# Audio_Keys.net
KiCad netlist of a schematic drawn in Altium Designer
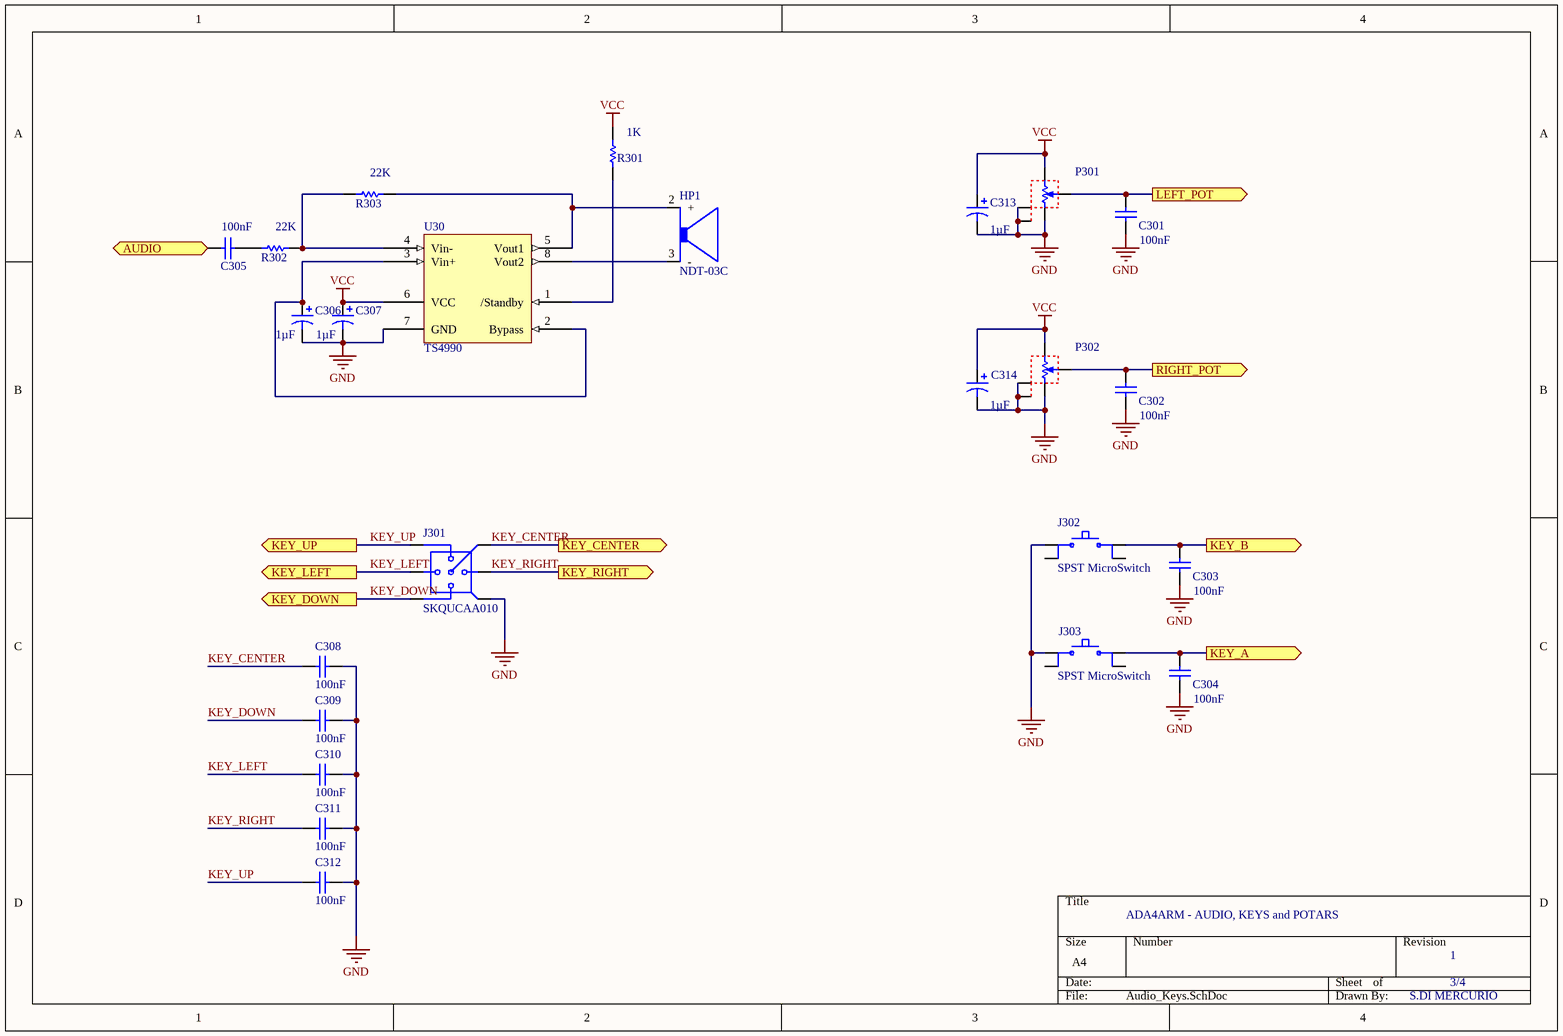
[diagram p0: Audio_Keys.SchDoc]

(export (version "E")
  (design (tool "Eeschema 10.0.6"))
  (components
    (comp (ref "C301")
      (value "100nF")
      (footprint "CAPC1206(3216)100_N")
      (description "CAP 100nF 16V -20% to +80% 1206 (3216 Metric) Thickness 1mm SMD")
      (fields (field (name "TOLERANCE") "-20% to +80%") (field (name "Comment") "CAP 100nF 16V 1206(3216)"))
      (libsource (lib "Altium Content Vault") (part "CMP-1037-04185-1"))
    )
    (comp (ref "C302")
      (value "100nF")
      (footprint "CAPC1206(3216)100_N")
      (description "CAP 100nF 16V -20% to +80% 1206 (3216 Metric) Thickness 1mm SMD")
      (fields (field (name "TOLERANCE") "-20% to +80%") (field (name "Comment") "CAP 100nF 16V 1206(3216)"))
      (libsource (lib "Altium Content Vault") (part "CMP-1037-04185-1"))
    )
    (comp (ref "C303")
      (value "100nF")
      (footprint "CAPC1206(3216)100_N")
      (description "CAP 100nF 16V -20% to +80% 1206 (3216 Metric) Thickness 1mm SMD")
      (fields (field (name "TOLERANCE") "-20% to +80%") (field (name "Comment") "CAP 100nF 16V 1206(3216)"))
      (libsource (lib "Altium Content Vault") (part "CMP-1037-04185-1"))
    )
    (comp (ref "C304")
      (value "100nF")
      (footprint "CAPC1206(3216)100_N")
      (description "CAP 100nF 16V -20% to +80% 1206 (3216 Metric) Thickness 1mm SMD")
      (fields (field (name "TOLERANCE") "-20% to +80%") (field (name "Comment") "CAP 100nF 16V 1206(3216)"))
      (libsource (lib "Altium Content Vault") (part "CMP-1037-04185-1"))
    )
    (comp (ref "C305")
      (value "100nF")
      (footprint "CAPC1206(3216)100_N")
      (description "CAP 100nF 16V -20% to +80% 1206 (3216 Metric) Thickness 1mm SMD")
      (fields (field (name "TOLERANCE") "-20% to +80%") (field (name "Comment") "CAP 100nF 16V 1206(3216)"))
      (libsource (lib "Altium Content Vault") (part "CMP-1037-04185-1"))
    )
    (comp (ref "C306")
      (value "1µF")
      (footprint "EAI 3216-18 A")
      (description "Polarized Capacitor (Surface Mount)")
      (fields (field (name "Comment") "Cap Pol3") (field (name "PUBLISHER") "Altium Limited"))
      (libsource (lib "Miscellaneous Devices") (part "Cap Pol3"))
    )
    (comp (ref "C307")
      (value "1µF")
      (footprint "EAI 3216-18 A")
      (description "Polarized Capacitor (Surface Mount)")
      (fields (field (name "Comment") "Cap Pol3") (field (name "PUBLISHER") "Altium Limited"))
      (libsource (lib "Miscellaneous Devices") (part "Cap Pol3"))
    )
    (comp (ref "C308")
      (value "100nF")
      (footprint "CAPC1206(3216)100_N")
      (description "CAP 100nF 16V -20% to +80% 1206 (3216 Metric) Thickness 1mm SMD")
      (fields (field (name "TOLERANCE") "-20% to +80%") (field (name "Comment") "CAP 100nF 16V 1206(3216)"))
      (libsource (lib "Altium Content Vault") (part "CMP-1037-04185-1"))
    )
    (comp (ref "C309")
      (value "100nF")
      (footprint "CAPC1206(3216)100_N")
      (description "CAP 100nF 16V -20% to +80% 1206 (3216 Metric) Thickness 1mm SMD")
      (fields (field (name "TOLERANCE") "-20% to +80%") (field (name "Comment") "CAP 100nF 16V 1206(3216)"))
      (libsource (lib "Altium Content Vault") (part "CMP-1037-04185-1"))
    )
    (comp (ref "C310")
      (value "100nF")
      (footprint "CAPC1206(3216)100_N")
      (description "CAP 100nF 16V -20% to +80% 1206 (3216 Metric) Thickness 1mm SMD")
      (fields (field (name "TOLERANCE") "-20% to +80%") (field (name "Comment") "CAP 100nF 16V 1206(3216)"))
      (libsource (lib "Altium Content Vault") (part "CMP-1037-04185-1"))
    )
    (comp (ref "C311")
      (value "100nF")
      (footprint "CAPC1206(3216)100_N")
      (description "CAP 100nF 16V -20% to +80% 1206 (3216 Metric) Thickness 1mm SMD")
      (fields (field (name "TOLERANCE") "-20% to +80%") (field (name "Comment") "CAP 100nF 16V 1206(3216)"))
      (libsource (lib "Altium Content Vault") (part "CMP-1037-04185-1"))
    )
    (comp (ref "C312")
      (value "100nF")
      (footprint "CAPC1206(3216)100_N")
      (description "CAP 100nF 16V -20% to +80% 1206 (3216 Metric) Thickness 1mm SMD")
      (fields (field (name "TOLERANCE") "-20% to +80%") (field (name "Comment") "CAP 100nF 16V 1206(3216)"))
      (libsource (lib "Altium Content Vault") (part "CMP-1037-04185-1"))
    )
    (comp (ref "C313")
      (value "1µF")
      (footprint "EAI 3216-18 A")
      (description "Polarized Capacitor (Surface Mount)")
      (fields (field (name "Comment") "Cap Pol3") (field (name "PUBLISHER") "Altium Limited"))
      (libsource (lib "Miscellaneous Devices") (part "Cap Pol3"))
    )
    (comp (ref "C314")
      (value "1µF")
      (footprint "EAI 3216-18 A")
      (description "Polarized Capacitor (Surface Mount)")
      (fields (field (name "Comment") "Cap Pol3") (field (name "PUBLISHER") "Altium Limited"))
      (libsource (lib "Miscellaneous Devices") (part "Cap Pol3"))
    )
    (comp (ref "HP1")
      (value "NDT-03C")
      (footprint "KAAG15008C")
      (description "Audio HP")
      (libsource (lib "INSA") (part "NDT-03C"))
    )
    (comp (ref "J301")
      (value "SKQUCAA010")
      (footprint "SKQUCAA010")
      (description "4 ways + center switch")
      (libsource (lib "INSA") (part "SKQUCAA010"))
    )
    (comp (ref "J302")
      (value "SPST MicroSwitch")
      (footprint "SPST_MicroSwitch")
      (description "SPST - MicroSwitch")
      (libsource (lib "INSA") (part "SPST MicroSwitch"))
    )
    (comp (ref "J303")
      (value "SPST MicroSwitch")
      (footprint "SPST_MicroSwitch")
      (description "SPST - MicroSwitch")
      (libsource (lib "INSA") (part "SPST MicroSwitch"))
    )
    (comp (ref "P301")
      (value "POT Type 51")
      (footprint "POT Type 51")
      (description "25mm Diameter potentiometer")
      (libsource (lib "INSA") (part "POT Type 51"))
    )
    (comp (ref "P302")
      (value "POT Type 51")
      (footprint "POT Type 51")
      (description "25mm Diameter potentiometer")
      (libsource (lib "INSA") (part "POT Type 51"))
    )
    (comp (ref "R301")
      (value "1K")
      (footprint "RESC1206(3216)_L")
      (description "10K 0.25W 1% 1206 (3216 Metric)  SMD")
      (fields (field (name "POWER") "0.25 W") (field (name "TOLERANCE") "1 %"))
      (libsource (lib "Altium Content Vault") (part "CMP-1014-00623-1"))
    )
    (comp (ref "R302")
      (value "22K")
      (footprint "RESC1206(3216)_L")
      (description "10K 0.25W 1% 1206 (3216 Metric)  SMD")
      (fields (field (name "POWER") "0.25 W") (field (name "TOLERANCE") "1 %"))
      (libsource (lib "Altium Content Vault") (part "CMP-1014-00623-1"))
    )
    (comp (ref "R303")
      (value "22K")
      (footprint "RESC1206(3216)_L")
      (description "10K 0.25W 1% 1206 (3216 Metric)  SMD")
      (fields (field (name "POWER") "0.25 W") (field (name "TOLERANCE") "1 %"))
      (libsource (lib "Altium Content Vault") (part "CMP-1014-00623-1"))
    )
    (comp (ref "U30") (value "TS4990") (footprint "MiniSOP-8") (libsource (lib "INSA") (part "TS4990")))
  )
  (nets
    (net (code "1") (name "/AUDIO") (class "Default")
      (node (ref "C305") (pin "2") (pinfunction "2_2") (pintype "passive"))
    )
    (net (code "2") (name "/KEY_A") (class "Default")
      (node (ref "C304") (pin "2") (pinfunction "2_2") (pintype "passive"))
      (node (ref "J303") (pin "3") (pinfunction "3_3") (pintype "passive"))
    )
    (net (code "3") (name "/KEY_B") (class "Default")
      (node (ref "C303") (pin "2") (pinfunction "2_2") (pintype "passive"))
      (node (ref "J302") (pin "3") (pinfunction "3_3") (pintype "passive"))
    )
    (net (code "4") (name "/KEY_CENTER") (class "Default")
      (node (ref "C308") (pin "1") (pinfunction "1_1") (pintype "passive"))
      (node (ref "J301") (pin "6") (pinfunction "CENTER_6") (pintype "passive"))
    )
    (net (code "5") (name "/KEY_DOWN") (class "Default")
      (node (ref "C309") (pin "1") (pinfunction "1_1") (pintype "passive"))
      (node (ref "J301") (pin "3") (pinfunction "DOWN_3") (pintype "passive"))
    )
    (net (code "6") (name "/KEY_LEFT") (class "Default")
      (node (ref "C310") (pin "1") (pinfunction "1_1") (pintype "passive"))
      (node (ref "J301") (pin "2") (pinfunction "LEFT_2") (pintype "passive"))
    )
    (net (code "7") (name "/KEY_RIGHT") (class "Default")
      (node (ref "C311") (pin "1") (pinfunction "1_1") (pintype "passive"))
      (node (ref "J301") (pin "5") (pinfunction "RIGHT_5") (pintype "passive"))
    )
    (net (code "8") (name "/KEY_UP") (class "Default")
      (node (ref "C312") (pin "1") (pinfunction "1_1") (pintype "passive"))
      (node (ref "J301") (pin "1") (pinfunction "UP_1") (pintype "passive"))
    )
    (net (code "9") (name "/LEFT_POT") (class "Default")
      (node (ref "C301") (pin "2") (pinfunction "2_2") (pintype "passive"))
      (node (ref "P301") (pin "2") (pinfunction "2_2") (pintype "passive"))
    )
    (net (code "10") (name "/RIGHT_POT") (class "Default")
      (node (ref "C302") (pin "2") (pinfunction "2_2") (pintype "passive"))
      (node (ref "P302") (pin "2") (pinfunction "2_2") (pintype "passive"))
    )
    (net (code "11") (name "GND") (class "Default")
      (node (ref "C301") (pin "1") (pinfunction "1_1") (pintype "passive"))
      (node (ref "C302") (pin "1") (pinfunction "1_1") (pintype "passive"))
      (node (ref "C303") (pin "1") (pinfunction "1_1") (pintype "passive"))
      (node (ref "C304") (pin "1") (pinfunction "1_1") (pintype "passive"))
      (node (ref "C306") (pin "2") (pinfunction "2_2") (pintype "passive"))
      (node (ref "C307") (pin "2") (pinfunction "2_2") (pintype "passive"))
      (node (ref "C308") (pin "2") (pinfunction "2_2") (pintype "passive"))
      (node (ref "C309") (pin "2") (pinfunction "2_2") (pintype "passive"))
      (node (ref "C310") (pin "2") (pinfunction "2_2") (pintype "passive"))
      (node (ref "C311") (pin "2") (pinfunction "2_2") (pintype "passive"))
      (node (ref "C312") (pin "2") (pinfunction "2_2") (pintype "passive"))
      (node (ref "C313") (pin "2") (pinfunction "2_2") (pintype "passive"))
      (node (ref "C314") (pin "2") (pinfunction "2_2") (pintype "passive"))
      (node (ref "J301") (pin "4") (pinfunction "COMMON_4") (pintype "passive"))
      (node (ref "J302") (pin "1") (pinfunction "1_1") (pintype "passive"))
      (node (ref "J303") (pin "1") (pinfunction "1_1") (pintype "passive"))
      (node (ref "P301") (pin "3") (pinfunction "3_3") (pintype "passive"))
      (node (ref "P301") (pin "4") (pinfunction "GND_4") (pintype "passive"))
      (node (ref "P301") (pin "5") (pinfunction "GND_5") (pintype "passive"))
      (node (ref "P302") (pin "3") (pinfunction "3_3") (pintype "passive"))
      (node (ref "P302") (pin "4") (pinfunction "GND_4") (pintype "passive"))
      (node (ref "P302") (pin "5") (pinfunction "GND_5") (pintype "passive"))
      (node (ref "U30") (pin "7") (pinfunction "GND_7") (pintype "power_in"))
    )
    (net (code "12") (name "Net-(C305-Pad1)") (class "Default")
      (node (ref "C305") (pin "1") (pinfunction "1_1") (pintype "passive"))
      (node (ref "R302") (pin "1") (pinfunction "1_1") (pintype "passive"))
    )
    (net (code "13") (name "Net-(HP1-+)") (class "Default")
      (node (ref "HP1") (pin "2") (pinfunction "+_2") (pintype "passive"))
      (node (ref "R303") (pin "2") (pinfunction "2_2") (pintype "passive"))
      (node (ref "U30") (pin "5") (pinfunction "Vout1_5") (pintype "output"))
    )
    (net (code "14") (name "Net-(HP1--)") (class "Default")
      (node (ref "HP1") (pin "3") (pinfunction "-_3") (pintype "passive"))
      (node (ref "U30") (pin "8") (pinfunction "Vout2_8") (pintype "output"))
    )
    (net (code "15") (name "Net-(U30-Bypass)") (class "Default")
      (node (ref "C306") (pin "1") (pinfunction "1_1") (pintype "passive"))
      (node (ref "U30") (pin "2") (pinfunction "Bypass_2") (pintype "input"))
      (node (ref "U30") (pin "3") (pinfunction "Vin+_3") (pintype "input"))
    )
    (net (code "16") (name "Net-(U30-Vin-)") (class "Default")
      (node (ref "R302") (pin "2") (pinfunction "2_2") (pintype "passive"))
      (node (ref "R303") (pin "1") (pinfunction "1_1") (pintype "passive"))
      (node (ref "U30") (pin "4") (pinfunction "Vin-_4") (pintype "input"))
    )
    (net (code "17") (name "Net-(U30-{slash}Standby)") (class "Default")
      (node (ref "R301") (pin "1") (pinfunction "1_1") (pintype "passive"))
      (node (ref "U30") (pin "1") (pinfunction "/Standby_1") (pintype "input"))
    )
    (net (code "18") (name "VCC") (class "Default")
      (node (ref "C307") (pin "1") (pinfunction "1_1") (pintype "passive"))
      (node (ref "C313") (pin "1") (pinfunction "1_1") (pintype "passive"))
      (node (ref "C314") (pin "1") (pinfunction "1_1") (pintype "passive"))
      (node (ref "P301") (pin "1") (pinfunction "1_1") (pintype "passive"))
      (node (ref "P302") (pin "1") (pinfunction "1_1") (pintype "passive"))
      (node (ref "R301") (pin "2") (pinfunction "2_2") (pintype "passive"))
      (node (ref "U30") (pin "6") (pinfunction "VCC_6") (pintype "power_in"))
    )
    (net (code "19") (name "unconnected-(J302-Pad2)") (class "Default")
      (node (ref "J302") (pin "2") (pinfunction "2_2") (pintype "passive"))
    )
    (net (code "20") (name "unconnected-(J302-Pad4)") (class "Default")
      (node (ref "J302") (pin "4") (pinfunction "4_4") (pintype "passive"))
    )
    (net (code "21") (name "unconnected-(J303-Pad2)") (class "Default")
      (node (ref "J303") (pin "2") (pinfunction "2_2") (pintype "passive"))
    )
    (net (code "22") (name "unconnected-(J303-Pad4)") (class "Default")
      (node (ref "J303") (pin "4") (pinfunction "4_4") (pintype "passive"))
    )
  )
)
